# EC20.net
KiCad netlist of a schematic drawn in Altium Designer
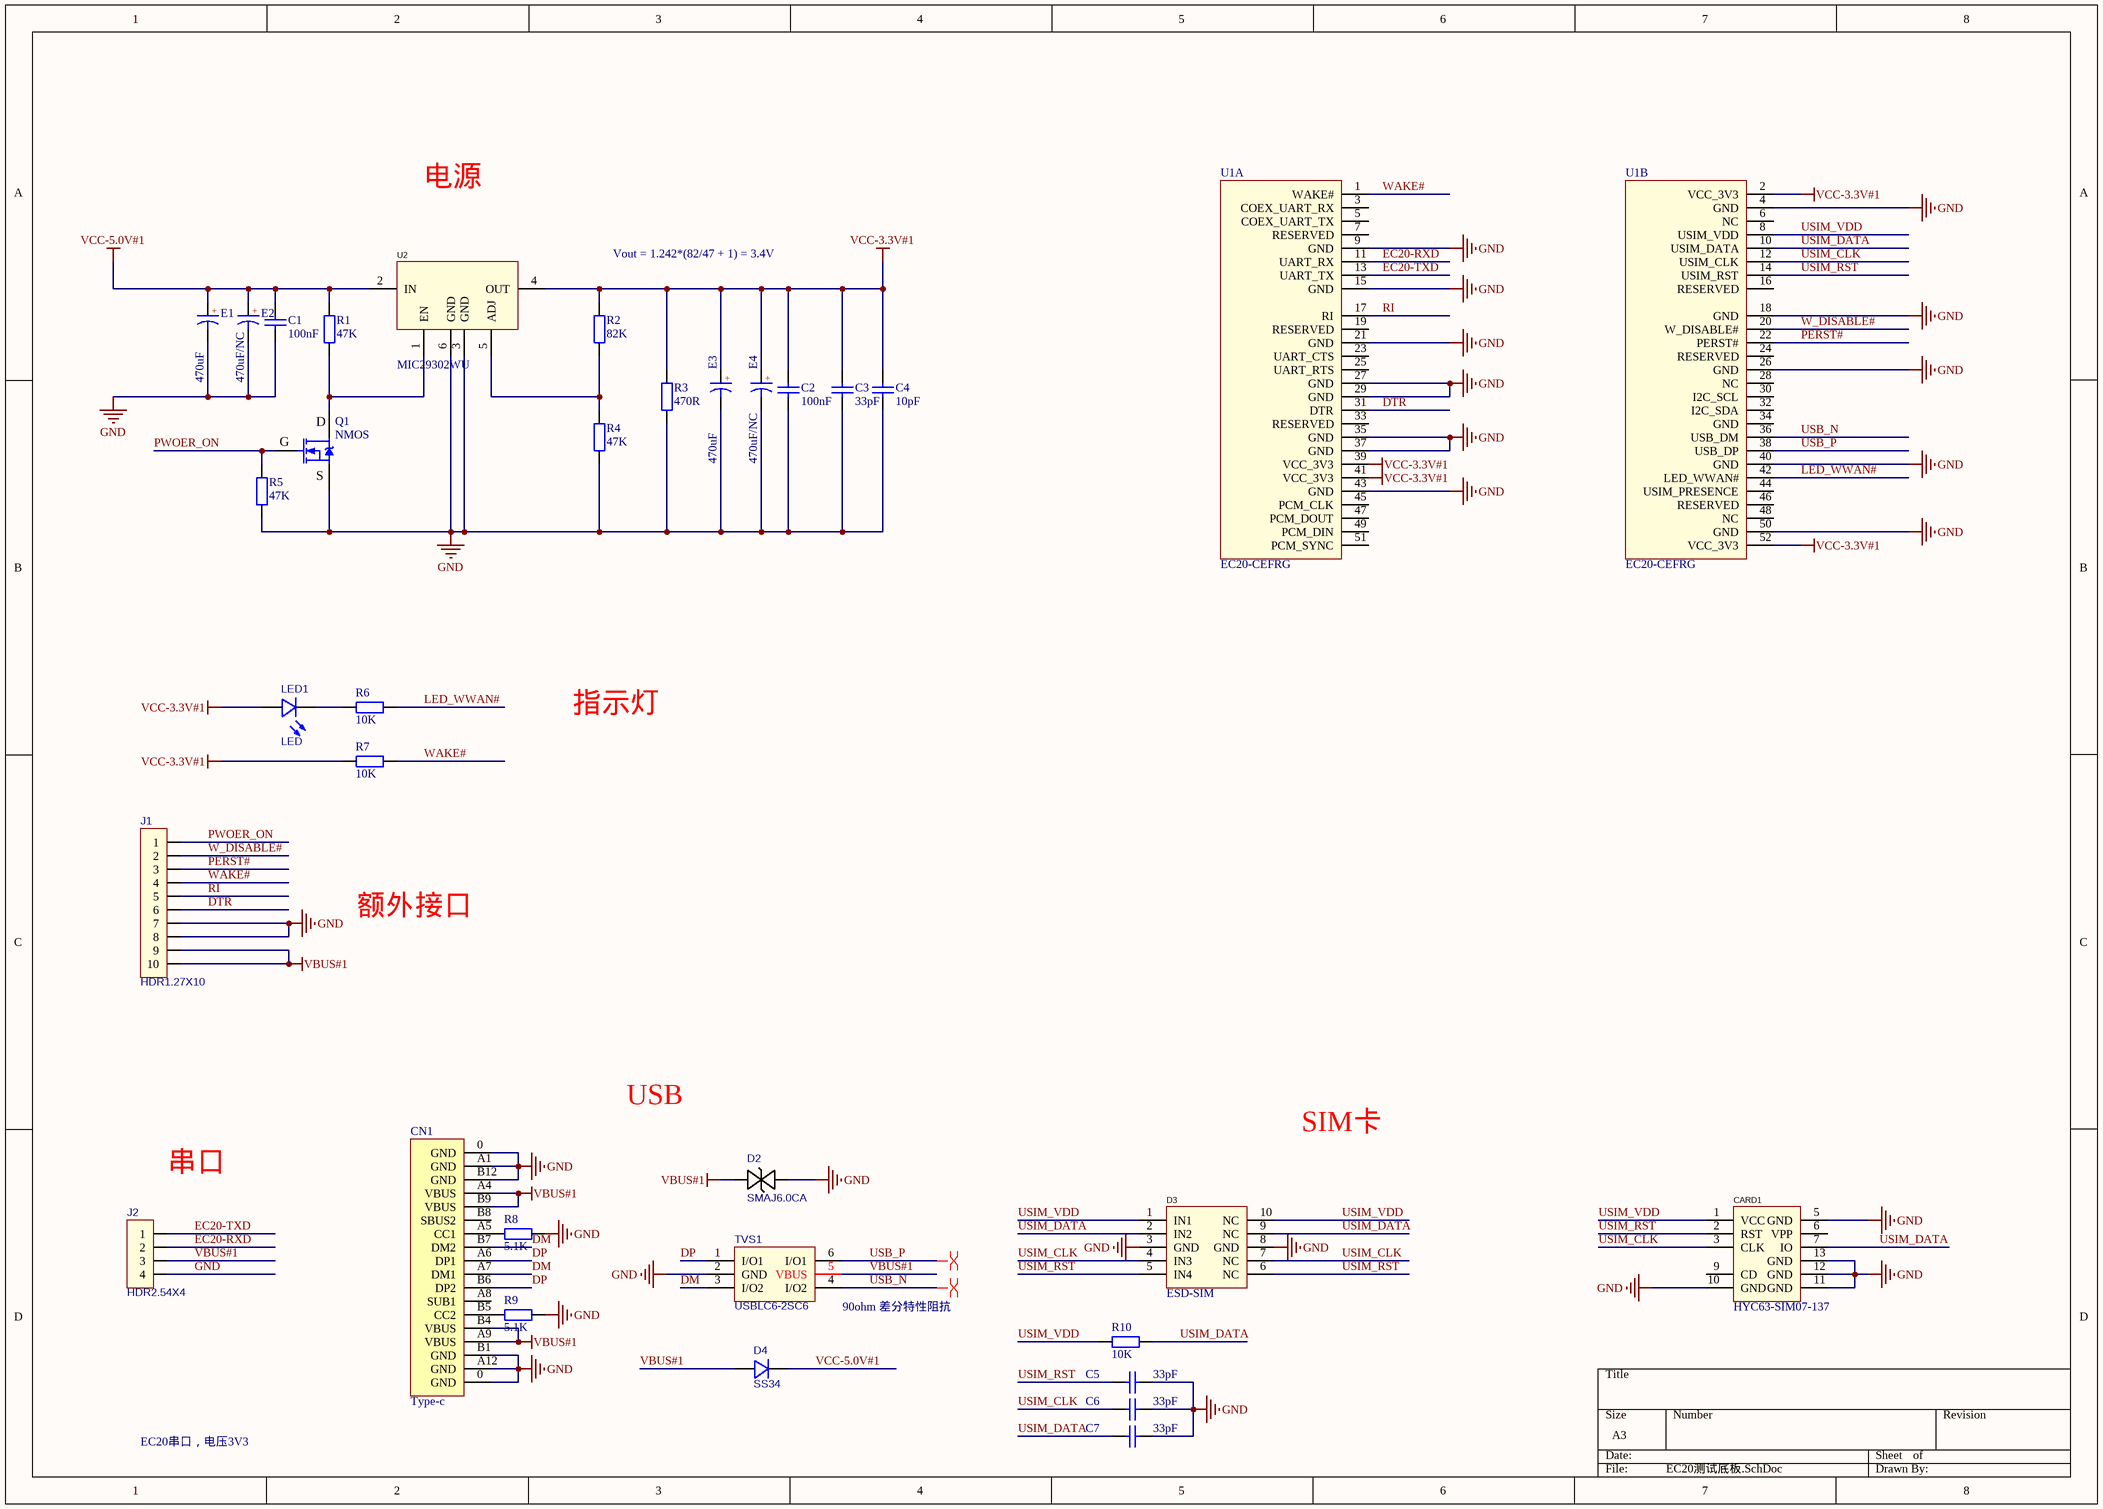
[diagram p0: EC20测试底板.SchDoc]

(export (version "E")
  (design (tool "Eeschema 10.0.6"))
  (components
    (comp (ref "C1")
      (value "100nF")
      (footprint "0603-C")
      (description "贴片电容")
      (libsource (lib "封装库") (part "C"))
    )
    (comp (ref "C2")
      (value "100nF")
      (footprint "0603-C")
      (description "贴片电容")
      (libsource (lib "封装库") (part "C"))
    )
    (comp (ref "C3")
      (value "33pF")
      (footprint "0603-C")
      (description "贴片电容")
      (libsource (lib "封装库") (part "C"))
    )
    (comp (ref "C4")
      (value "10pF")
      (footprint "0603-C")
      (description "贴片电容")
      (libsource (lib "封装库") (part "C"))
    )
    (comp (ref "C5")
      (value "33pF")
      (footprint "0603-C")
      (description "贴片电容")
      (libsource (lib "封装库") (part "C"))
    )
    (comp (ref "C6")
      (value "33pF")
      (footprint "0603-C")
      (description "贴片电容")
      (libsource (lib "封装库") (part "C"))
    )
    (comp (ref "C7")
      (value "33pF")
      (footprint "0603-C")
      (description "贴片电容")
      (libsource (lib "封装库") (part "C"))
    )
    (comp (ref "CARD1")
      (value "HYC63-SIM07-137")
      (footprint "NANO-SIM-SMD_HYC63-SIM07-137")
      (description "自弹式 NanoSIM卡 卡座 带CD PIN 带柱")
      (fields (field (name "MANUFACTURER") "华宇创"))
      (libsource (lib "封装库") (part "NanoSIM卡座"))
    )
    (comp (ref "CN1")
      (value "Type-c")
      (footprint "Type-c 16pin")
      (description "U262-161N-4BVC11")
      (libsource (lib "封装库") (part "Type-c"))
    )
    (comp (ref "D2")
      (value "SMAJ6.0CA")
      (footprint "ZENER")
      (description "SMAJ6.0CA_C698928")
      (fields (field (name "BOM_SUPPLIER PART") "C698928") (field (name "CONTRIBUTOR") "LCSC"))
      (libsource (lib "封装库") (part "SMAJ6.0CA"))
    )
    (comp (ref "D3")
      (value "ESD-SIM")
      (footprint "SLP2510P8")
      (description "RClamp0524PATCT")
      (fields (field (name "MANUFACTURER") "SEMTECH"))
      (libsource (lib "封装库") (part "ESD-SIM"))
    )
    (comp (ref "D4")
      (value "SS34")
      (footprint "SS34-SMA")
      (fields
        (field (name "BOM_SUPPLIER PART") "C118334")
        (field (name "BOM_MANUFACTURER PART") "D-G060306G1-KS2")
        (field (name "CONTRIBUTOR") "LCSC")
      )
      (libsource (lib "封装库") (part "SS34"))
    )
    (comp (ref "E1")
      (value "470uF")
      (footprint "CD D(7343)")
      (description "贴片钽电容")
      (libsource (lib "封装库") (part "CT"))
    )
    (comp (ref "E2")
      (value "470uF/NC")
      (footprint "CD D(7343)")
      (description "贴片钽电容")
      (libsource (lib "封装库") (part "CT"))
    )
    (comp (ref "E3")
      (value "470uF")
      (footprint "CD D(7343)")
      (description "贴片钽电容")
      (libsource (lib "封装库") (part "CT"))
    )
    (comp (ref "E4")
      (value "470uF/NC")
      (footprint "CD D(7343)")
      (description "贴片钽电容")
      (libsource (lib "封装库") (part "CT"))
    )
    (comp (ref "J1")
      (value "HDR1.27X10")
      (footprint "HDR2.54-LI-10P")
      (fields
        (field (name "BOM_MANUFACTURER PART") "1.27mm/1*3p")
        (field (name "BOM_SUPPLIER PART") "C24980")
      )
      (libsource (lib "封装库") (part "HDR2.54X10"))
    )
    (comp (ref "J2")
      (value "HDR2.54X4")
      (footprint "HDR2.54-LI-4P")
      (fields
        (field (name "BOM_MANUFACTURER PART") "1.27mm/1*3p")
        (field (name "BOM_SUPPLIER PART") "C24980")
      )
      (libsource (lib "封装库") (part "HDR2.54X4"))
    )
    (comp (ref "LED1")
      (value "LED")
      (footprint "LED-0603")
      (fields
        (field (name "BOM_SUPPLIER PART") "C118334")
        (field (name "BOM_MANUFACTURER PART") "D-G060306G1-KS2")
        (field (name "CONTRIBUTOR") "LCSC")
      )
      (libsource (lib "封装库") (part "LED"))
    )
    (comp (ref "Q1")
      (value "NMOS")
      (footprint "AO3400")
      (description "N沟道 30V/4.2A")
      (libsource (lib "封装库") (part "AO3400"))
    )
    (comp (ref "R1")
      (value "47K")
      (footprint "0603-R")
      (description "贴片电阻")
      (libsource (lib "封装库") (part "R"))
    )
    (comp (ref "R2")
      (value "82K")
      (footprint "0603-R")
      (description "贴片电阻")
      (libsource (lib "封装库") (part "R"))
    )
    (comp (ref "R3")
      (value "470R")
      (footprint "0603-R")
      (description "贴片电阻")
      (libsource (lib "封装库") (part "R"))
    )
    (comp (ref "R4")
      (value "47K")
      (footprint "0603-R")
      (description "贴片电阻")
      (libsource (lib "封装库") (part "R"))
    )
    (comp (ref "R5")
      (value "47K")
      (footprint "0603-R")
      (description "贴片电阻")
      (libsource (lib "封装库") (part "R"))
    )
    (comp (ref "R6")
      (value "10K")
      (footprint "0603-R")
      (description "贴片电阻")
      (libsource (lib "封装库") (part "R"))
    )
    (comp (ref "R7")
      (value "10K")
      (footprint "0603-R")
      (description "贴片电阻")
      (libsource (lib "封装库") (part "R"))
    )
    (comp (ref "R8")
      (value "5.1K")
      (footprint "0603-R")
      (description "贴片电阻")
      (libsource (lib "封装库") (part "R"))
    )
    (comp (ref "R9")
      (value "5.1K")
      (footprint "0603-R")
      (description "贴片电阻")
      (libsource (lib "封装库") (part "R"))
    )
    (comp (ref "R10")
      (value "10K")
      (footprint "0603-R")
      (description "贴片电阻")
      (libsource (lib "封装库") (part "R"))
    )
    (comp (ref "TVS1")
      (value "USBLC6-2SC6")
      (footprint "USBLC6-2")
      (description "USBLC6-2SC6_C2687116")
      (fields (field (name "BOM_SUPPLIER PART") "C2687116") (field (name "CONTRIBUTOR") "LCSC"))
      (libsource (lib "封装库") (part "USBLC6-2SC6"))
    )
    (comp (ref "U1")
      (value "EC20-CEFRG")
      (footprint "mini-PCI_E接口")
      (libsource (lib "封装库") (part "EC20-CEFRG"))
    )
    (comp (ref "U2")
      (value "MIC29302WU")
      (footprint "MIC29302WU")
      (fields (field (name "MANUFACTURER") "UMW(友台半导体)"))
      (libsource (lib "封装库") (part "MIC29302WU"))
    )
  )
  (nets
    (net (code "1") (name "/DM") (class "Default")
      (node (ref "CN1") (pin "A7") (pinfunction "DM1_A7") (pintype "passive"))
      (node (ref "CN1") (pin "B7") (pinfunction "DM2_B7") (pintype "passive"))
      (node (ref "TVS1") (pin "3") (pinfunction "I/O2_3") (pintype "passive"))
    )
    (net (code "2") (name "/DP") (class "Default")
      (node (ref "CN1") (pin "A6") (pinfunction "DP1_A6") (pintype "passive"))
      (node (ref "CN1") (pin "B6") (pinfunction "DP2_B6") (pintype "passive"))
      (node (ref "TVS1") (pin "1") (pinfunction "I/O1_1") (pintype "passive"))
    )
    (net (code "3") (name "/DTR") (class "Default")
      (node (ref "J1") (pin "6") (pinfunction "6_6") (pintype "passive"))
      (node (ref "U1") (pin "31") (pinfunction "DTR_31") (pintype "passive"))
    )
    (net (code "4") (name "/EC20-RXD") (class "Default")
      (node (ref "J2") (pin "2") (pinfunction "2_2") (pintype "passive"))
      (node (ref "U1") (pin "11") (pinfunction "UART_RX_11") (pintype "passive"))
    )
    (net (code "5") (name "/EC20-TXD") (class "Default")
      (node (ref "J2") (pin "1") (pinfunction "1_1") (pintype "passive"))
      (node (ref "U1") (pin "13") (pinfunction "UART_TX_13") (pintype "passive"))
    )
    (net (code "6") (name "/LED_WWAN#") (class "Default")
      (node (ref "R6") (pin "1") (pinfunction "1_1") (pintype "passive"))
      (node (ref "U1") (pin "42") (pinfunction "LED_WWAN#_42") (pintype "passive"))
    )
    (net (code "7") (name "/PERST#") (class "Default")
      (node (ref "J1") (pin "3") (pinfunction "3_3") (pintype "passive"))
      (node (ref "U1") (pin "22") (pinfunction "PERST#_22") (pintype "passive"))
    )
    (net (code "8") (name "/PWOER_ON") (class "Default")
      (node (ref "J1") (pin "1") (pinfunction "1_1") (pintype "passive"))
      (node (ref "Q1") (pin "1") (pinfunction "G_1") (pintype "passive"))
      (node (ref "R5") (pin "2") (pinfunction "2_2") (pintype "passive"))
    )
    (net (code "9") (name "/RI") (class "Default")
      (node (ref "J1") (pin "5") (pinfunction "5_5") (pintype "passive"))
      (node (ref "U1") (pin "17") (pinfunction "RI_17") (pintype "passive"))
    )
    (net (code "10") (name "/USB_N") (class "Default")
      (node (ref "TVS1") (pin "4") (pinfunction "I/O2_4") (pintype "passive"))
      (node (ref "U1") (pin "36") (pinfunction "USB_DM_36") (pintype "passive"))
    )
    (net (code "11") (name "/USB_P") (class "Default")
      (node (ref "TVS1") (pin "6") (pinfunction "I/O1_6") (pintype "passive"))
      (node (ref "U1") (pin "38") (pinfunction "USB_DP_38") (pintype "passive"))
    )
    (net (code "12") (name "/USIM_CLK") (class "Default")
      (node (ref "C6") (pin "2") (pinfunction "2_2") (pintype "passive"))
      (node (ref "CARD1") (pin "3") (pinfunction "CLK_3") (pintype "passive"))
      (node (ref "D3") (pin "4") (pinfunction "IN3_4") (pintype "passive"))
      (node (ref "D3") (pin "7") (pinfunction "NC_7") (pintype "passive"))
      (node (ref "U1") (pin "12") (pinfunction "USIM_CLK_12") (pintype "passive"))
    )
    (net (code "13") (name "/USIM_DATA") (class "Default")
      (node (ref "C7") (pin "2") (pinfunction "2_2") (pintype "passive"))
      (node (ref "CARD1") (pin "7") (pinfunction "IO_7") (pintype "passive"))
      (node (ref "D3") (pin "2") (pinfunction "IN2_2") (pintype "passive"))
      (node (ref "D3") (pin "9") (pinfunction "NC_9") (pintype "passive"))
      (node (ref "R10") (pin "1") (pinfunction "1_1") (pintype "passive"))
      (node (ref "U1") (pin "10") (pinfunction "USIM_DATA_10") (pintype "passive"))
    )
    (net (code "14") (name "/USIM_RST") (class "Default")
      (node (ref "C5") (pin "2") (pinfunction "2_2") (pintype "passive"))
      (node (ref "CARD1") (pin "2") (pinfunction "RST_2") (pintype "passive"))
      (node (ref "D3") (pin "5") (pinfunction "IN4_5") (pintype "passive"))
      (node (ref "D3") (pin "6") (pinfunction "NC_6") (pintype "passive"))
      (node (ref "U1") (pin "14") (pinfunction "USIM_RST_14") (pintype "passive"))
    )
    (net (code "15") (name "/USIM_VDD") (class "Default")
      (node (ref "CARD1") (pin "1") (pinfunction "VCC_1") (pintype "passive"))
      (node (ref "D3") (pin "1") (pinfunction "IN1_1") (pintype "passive"))
      (node (ref "D3") (pin "10") (pinfunction "NC_10") (pintype "passive"))
      (node (ref "R10") (pin "2") (pinfunction "2_2") (pintype "passive"))
      (node (ref "U1") (pin "8") (pinfunction "USIM_VDD_8") (pintype "passive"))
    )
    (net (code "16") (name "/WAKE#") (class "Default")
      (node (ref "J1") (pin "4") (pinfunction "4_4") (pintype "passive"))
      (node (ref "R7") (pin "1") (pinfunction "1_1") (pintype "passive"))
      (node (ref "U1") (pin "1") (pinfunction "WAKE#_1") (pintype "passive"))
    )
    (net (code "17") (name "/W_DISABLE#") (class "Default")
      (node (ref "J1") (pin "2") (pinfunction "2_2") (pintype "passive"))
      (node (ref "U1") (pin "20") (pinfunction "W_DISABLE#_20") (pintype "passive"))
    )
    (net (code "18") (name "GND") (class "Default")
      (node (ref "C1") (pin "1") (pinfunction "1_1") (pintype "passive"))
      (node (ref "C2") (pin "1") (pinfunction "1_1") (pintype "passive"))
      (node (ref "C3") (pin "1") (pinfunction "1_1") (pintype "passive"))
      (node (ref "C4") (pin "1") (pinfunction "1_1") (pintype "passive"))
      (node (ref "C5") (pin "1") (pinfunction "1_1") (pintype "passive"))
      (node (ref "C6") (pin "1") (pinfunction "1_1") (pintype "passive"))
      (node (ref "C7") (pin "1") (pinfunction "1_1") (pintype "passive"))
      (node (ref "CARD1") (pin "10") (pinfunction "GND_10") (pintype "passive"))
      (node (ref "CARD1") (pin "11") (pinfunction "GND_11") (pintype "passive"))
      (node (ref "CARD1") (pin "12") (pinfunction "GND_12") (pintype "passive"))
      (node (ref "CARD1") (pin "13") (pinfunction "GND_13") (pintype "passive"))
      (node (ref "CARD1") (pin "5") (pinfunction "GND_5") (pintype "passive"))
      (node (ref "CN1") (pin "0") (pinfunction "GND_0") (pintype "passive"))
      (node (ref "CN1") (pin "A1") (pinfunction "GND_A1") (pintype "passive"))
      (node (ref "CN1") (pin "A12") (pinfunction "GND_A12") (pintype "passive"))
      (node (ref "CN1") (pin "B1") (pinfunction "GND_B1") (pintype "passive"))
      (node (ref "CN1") (pin "B12") (pinfunction "GND_B12") (pintype "passive"))
      (node (ref "D2") (pin "2") (pinfunction "A_2") (pintype "passive"))
      (node (ref "D3") (pin "3") (pinfunction "GND_3") (pintype "passive"))
      (node (ref "D3") (pin "8") (pinfunction "GND_8") (pintype "passive"))
      (node (ref "E1") (pin "2") (pinfunction "K_2") (pintype "passive"))
      (node (ref "E2") (pin "2") (pinfunction "K_2") (pintype "passive"))
      (node (ref "E3") (pin "2") (pinfunction "K_2") (pintype "passive"))
      (node (ref "E4") (pin "2") (pinfunction "K_2") (pintype "passive"))
      (node (ref "J1") (pin "7") (pinfunction "7_7") (pintype "passive"))
      (node (ref "J1") (pin "8") (pinfunction "8_8") (pintype "passive"))
      (node (ref "J2") (pin "4") (pinfunction "4_4") (pintype "passive"))
      (node (ref "Q1") (pin "2") (pinfunction "S_2") (pintype "passive"))
      (node (ref "R3") (pin "1") (pinfunction "1_1") (pintype "passive"))
      (node (ref "R4") (pin "1") (pinfunction "1_1") (pintype "passive"))
      (node (ref "R5") (pin "1") (pinfunction "1_1") (pintype "passive"))
      (node (ref "R8") (pin "1") (pinfunction "1_1") (pintype "passive"))
      (node (ref "R9") (pin "2") (pinfunction "2_2") (pintype "passive"))
      (node (ref "TVS1") (pin "2") (pinfunction "GND_2") (pintype "passive"))
      (node (ref "U1") (pin "15") (pinfunction "GND_15") (pintype "passive"))
      (node (ref "U1") (pin "18") (pinfunction "GND_18") (pintype "passive"))
      (node (ref "U1") (pin "21") (pinfunction "GND_21") (pintype "passive"))
      (node (ref "U1") (pin "26") (pinfunction "GND_26") (pintype "passive"))
      (node (ref "U1") (pin "27") (pinfunction "GND_27") (pintype "passive"))
      (node (ref "U1") (pin "29") (pinfunction "GND_29") (pintype "passive"))
      (node (ref "U1") (pin "35") (pinfunction "GND_35") (pintype "passive"))
      (node (ref "U1") (pin "37") (pinfunction "GND_37") (pintype "passive"))
      (node (ref "U1") (pin "4") (pinfunction "GND_4") (pintype "passive"))
      (node (ref "U1") (pin "40") (pinfunction "GND_40") (pintype "passive"))
      (node (ref "U1") (pin "43") (pinfunction "GND_43") (pintype "passive"))
      (node (ref "U1") (pin "50") (pinfunction "GND_50") (pintype "passive"))
      (node (ref "U1") (pin "9") (pinfunction "GND_9") (pintype "passive"))
      (node (ref "U2") (pin "3") (pinfunction "GND_3") (pintype "passive"))
      (node (ref "U2") (pin "6") (pinfunction "GND_6") (pintype "passive"))
    )
    (net (code "19") (name "Net-(CN1-CC1)") (class "Default")
      (node (ref "CN1") (pin "A5") (pinfunction "CC1_A5") (pintype "passive"))
      (node (ref "R8") (pin "2") (pinfunction "2_2") (pintype "passive"))
    )
    (net (code "20") (name "Net-(CN1-CC2)") (class "Default")
      (node (ref "CN1") (pin "B5") (pinfunction "CC2_B5") (pintype "passive"))
      (node (ref "R9") (pin "1") (pinfunction "1_1") (pintype "passive"))
    )
    (net (code "21") (name "Net-(LED1--)") (class "Default")
      (node (ref "LED1") (pin "1") (pinfunction "-_1") (pintype "passive"))
      (node (ref "R6") (pin "2") (pinfunction "2_2") (pintype "passive"))
    )
    (net (code "22") (name "Net-(Q1-D)") (class "Default")
      (node (ref "Q1") (pin "3") (pinfunction "D_3") (pintype "passive"))
      (node (ref "R1") (pin "1") (pinfunction "1_1") (pintype "passive"))
      (node (ref "U2") (pin "1") (pinfunction "EN_1") (pintype "passive"))
    )
    (net (code "23") (name "Net-(U2-ADJ)") (class "Default")
      (node (ref "R2") (pin "1") (pinfunction "1_1") (pintype "passive"))
      (node (ref "R4") (pin "2") (pinfunction "2_2") (pintype "passive"))
      (node (ref "U2") (pin "5") (pinfunction "ADJ_5") (pintype "passive"))
    )
    (net (code "24") (name "VBUS#1") (class "Default")
      (node (ref "CN1") (pin "A4") (pinfunction "VBUS_A4") (pintype "passive"))
      (node (ref "CN1") (pin "A9") (pinfunction "VBUS_A9") (pintype "passive"))
      (node (ref "CN1") (pin "B4") (pinfunction "VBUS_B4") (pintype "passive"))
      (node (ref "CN1") (pin "B9") (pinfunction "VBUS_B9") (pintype "passive"))
      (node (ref "D2") (pin "1") (pinfunction "C_1") (pintype "passive"))
      (node (ref "D4") (pin "1") (pinfunction "+_1") (pintype "passive"))
      (node (ref "J1") (pin "10") (pinfunction "10_10") (pintype "passive"))
      (node (ref "J1") (pin "9") (pinfunction "9_9") (pintype "passive"))
      (node (ref "J2") (pin "3") (pinfunction "3_3") (pintype "passive"))
      (node (ref "TVS1") (pin "5") (pinfunction "VBUS_5") (pintype "passive"))
    )
    (net (code "25") (name "VCC-3.3V#1") (class "Default")
      (node (ref "C2") (pin "2") (pinfunction "2_2") (pintype "passive"))
      (node (ref "C3") (pin "2") (pinfunction "2_2") (pintype "passive"))
      (node (ref "C4") (pin "2") (pinfunction "2_2") (pintype "passive"))
      (node (ref "E3") (pin "1") (pinfunction "A_1") (pintype "passive"))
      (node (ref "E4") (pin "1") (pinfunction "A_1") (pintype "passive"))
      (node (ref "LED1") (pin "2") (pinfunction "+_2") (pintype "passive"))
      (node (ref "R2") (pin "2") (pinfunction "2_2") (pintype "passive"))
      (node (ref "R3") (pin "2") (pinfunction "2_2") (pintype "passive"))
      (node (ref "R7") (pin "2") (pinfunction "2_2") (pintype "passive"))
      (node (ref "U1") (pin "2") (pinfunction "VCC_3V3_2") (pintype "passive"))
      (node (ref "U1") (pin "39") (pinfunction "VCC_3V3_39") (pintype "passive"))
      (node (ref "U1") (pin "41") (pinfunction "VCC_3V3_41") (pintype "passive"))
      (node (ref "U1") (pin "52") (pinfunction "VCC_3V3_52") (pintype "passive"))
      (node (ref "U2") (pin "4") (pinfunction "OUT_4") (pintype "passive"))
    )
    (net (code "26") (name "VCC-5.0V#1") (class "Default")
      (node (ref "C1") (pin "2") (pinfunction "2_2") (pintype "passive"))
      (node (ref "D4") (pin "2") (pinfunction "-_2") (pintype "passive"))
      (node (ref "E1") (pin "1") (pinfunction "A_1") (pintype "passive"))
      (node (ref "E2") (pin "1") (pinfunction "A_1") (pintype "passive"))
      (node (ref "R1") (pin "2") (pinfunction "2_2") (pintype "passive"))
      (node (ref "U2") (pin "2") (pinfunction "IN_2") (pintype "passive"))
    )
    (net (code "27") (name "unconnected-(CARD1-CD-Pad9)") (class "Default")
      (node (ref "CARD1") (pin "9") (pinfunction "CD_9") (pintype "passive"))
    )
    (net (code "28") (name "unconnected-(CARD1-VPP-Pad6)") (class "Default")
      (node (ref "CARD1") (pin "6") (pinfunction "VPP_6") (pintype "passive"))
    )
    (net (code "29") (name "unconnected-(CN1-SBUS2-PadB8)") (class "Default")
      (node (ref "CN1") (pin "B8") (pinfunction "SBUS2_B8") (pintype "passive"))
    )
    (net (code "30") (name "unconnected-(CN1-SUB1-PadA8)") (class "Default")
      (node (ref "CN1") (pin "A8") (pinfunction "SUB1_A8") (pintype "passive"))
    )
    (net (code "31") (name "unconnected-(U1A-COEX_UART_RX-Pad3)") (class "Default")
      (node (ref "U1") (pin "3") (pinfunction "COEX_UART_RX_3") (pintype "passive"))
    )
    (net (code "32") (name "unconnected-(U1A-COEX_UART_TX-Pad5)") (class "Default")
      (node (ref "U1") (pin "5") (pinfunction "COEX_UART_TX_5") (pintype "passive"))
    )
    (net (code "33") (name "unconnected-(U1A-PCM_CLK-Pad45)") (class "Default")
      (node (ref "U1") (pin "45") (pinfunction "PCM_CLK_45") (pintype "passive"))
    )
    (net (code "34") (name "unconnected-(U1A-PCM_DIN-Pad49)") (class "Default")
      (node (ref "U1") (pin "49") (pinfunction "PCM_DIN_49") (pintype "passive"))
    )
    (net (code "35") (name "unconnected-(U1A-PCM_DOUT-Pad47)") (class "Default")
      (node (ref "U1") (pin "47") (pinfunction "PCM_DOUT_47") (pintype "passive"))
    )
    (net (code "36") (name "unconnected-(U1A-PCM_SYNC-Pad51)") (class "Default")
      (node (ref "U1") (pin "51") (pinfunction "PCM_SYNC_51") (pintype "passive"))
    )
    (net (code "37") (name "unconnected-(U1A-RESERVED-Pad7)") (class "Default")
      (node (ref "U1") (pin "7") (pinfunction "RESERVED_7") (pintype "passive"))
    )
    (net (code "38") (name "unconnected-(U1A-RESERVED-Pad19)") (class "Default")
      (node (ref "U1") (pin "19") (pinfunction "RESERVED_19") (pintype "passive"))
    )
    (net (code "39") (name "unconnected-(U1A-RESERVED-Pad33)") (class "Default")
      (node (ref "U1") (pin "33") (pinfunction "RESERVED_33") (pintype "passive"))
    )
    (net (code "40") (name "unconnected-(U1A-UART_CTS-Pad23)") (class "Default")
      (node (ref "U1") (pin "23") (pinfunction "UART_CTS_23") (pintype "passive"))
    )
    (net (code "41") (name "unconnected-(U1A-UART_RTS-Pad25)") (class "Default")
      (node (ref "U1") (pin "25") (pinfunction "UART_RTS_25") (pintype "passive"))
    )
    (net (code "42") (name "unconnected-(U1B-GND-Pad34)") (class "Default")
      (node (ref "U1") (pin "34") (pinfunction "GND_34") (pintype "passive"))
    )
    (net (code "43") (name "unconnected-(U1B-I2C_SCL-Pad30)") (class "Default")
      (node (ref "U1") (pin "30") (pinfunction "I2C_SCL_30") (pintype "passive"))
    )
    (net (code "44") (name "unconnected-(U1B-I2C_SDA-Pad32)") (class "Default")
      (node (ref "U1") (pin "32") (pinfunction "I2C_SDA_32") (pintype "passive"))
    )
    (net (code "45") (name "unconnected-(U1B-NC-Pad6)") (class "Default")
      (node (ref "U1") (pin "6") (pinfunction "NC_6") (pintype "passive"))
    )
    (net (code "46") (name "unconnected-(U1B-NC-Pad28)") (class "Default")
      (node (ref "U1") (pin "28") (pinfunction "NC_28") (pintype "passive"))
    )
    (net (code "47") (name "unconnected-(U1B-NC-Pad48)") (class "Default")
      (node (ref "U1") (pin "48") (pinfunction "NC_48") (pintype "passive"))
    )
    (net (code "48") (name "unconnected-(U1B-RESERVED-Pad16)") (class "Default")
      (node (ref "U1") (pin "16") (pinfunction "RESERVED_16") (pintype "passive"))
    )
    (net (code "49") (name "unconnected-(U1B-RESERVED-Pad24)") (class "Default")
      (node (ref "U1") (pin "24") (pinfunction "RESERVED_24") (pintype "passive"))
    )
    (net (code "50") (name "unconnected-(U1B-RESERVED-Pad46)") (class "Default")
      (node (ref "U1") (pin "46") (pinfunction "RESERVED_46") (pintype "passive"))
    )
    (net (code "51") (name "unconnected-(U1B-USIM_PRESENCE-Pad44)") (class "Default")
      (node (ref "U1") (pin "44") (pinfunction "USIM_PRESENCE_44") (pintype "passive"))
    )
  )
)
